# untitled.net
KiCad netlist of a schematic drawn in EAGLE
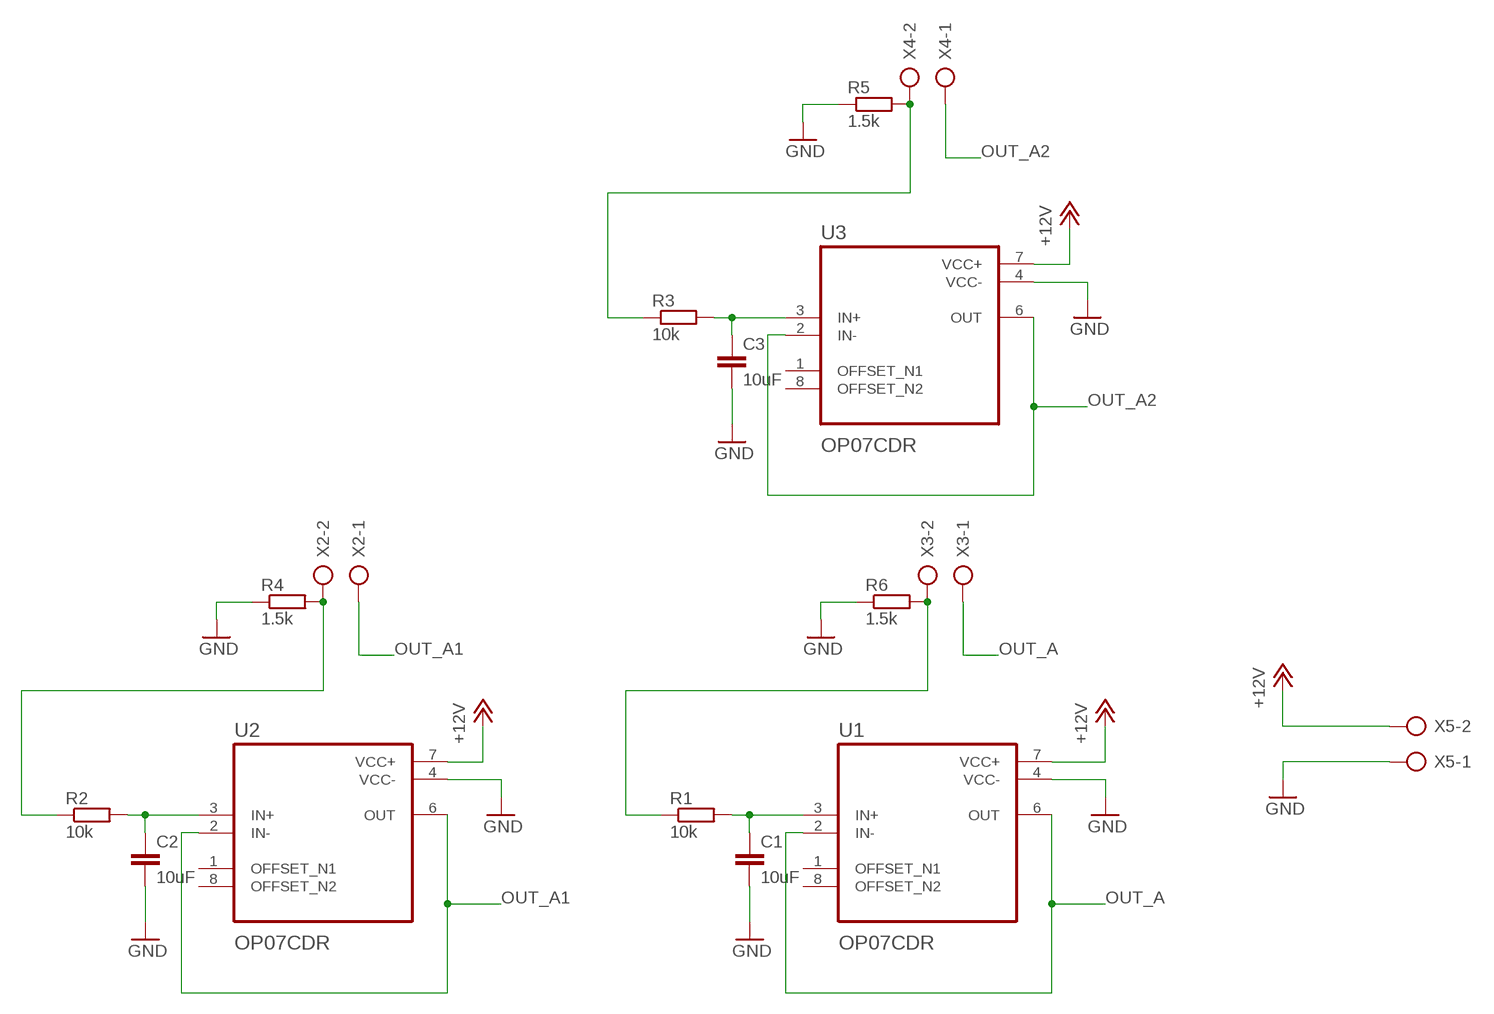
[diagram p0: schematic, sheet 1]

(export (version "E")
  (design (tool "Eeschema 10.0.6"))
  (components
    (comp (ref "C1")
      (value "10uF")
      (footprint "eagle-import:C0805")
      (libsource (lib "eagle-import") (part "C-EUC0805"))
    )
    (comp (ref "C2")
      (value "10uF")
      (footprint "eagle-import:C0805")
      (libsource (lib "eagle-import") (part "C-EUC0805"))
    )
    (comp (ref "C3")
      (value "10uF")
      (footprint "eagle-import:C0805")
      (libsource (lib "eagle-import") (part "C-EUC0805"))
    )
    (comp (ref "R1")
      (value "10k")
      (footprint "eagle-import:M0805")
      (libsource (lib "eagle-import") (part "R-EU_M0805"))
    )
    (comp (ref "R2")
      (value "10k")
      (footprint "eagle-import:M0805")
      (libsource (lib "eagle-import") (part "R-EU_M0805"))
    )
    (comp (ref "R3")
      (value "10k")
      (footprint "eagle-import:M0805")
      (libsource (lib "eagle-import") (part "R-EU_M0805"))
    )
    (comp (ref "R4")
      (value "1.5k")
      (footprint "eagle-import:M0805")
      (libsource (lib "eagle-import") (part "R-EU_M0805"))
    )
    (comp (ref "R5")
      (value "1.5k")
      (footprint "eagle-import:M0805")
      (libsource (lib "eagle-import") (part "R-EU_M0805"))
    )
    (comp (ref "R6")
      (value "1.5k")
      (footprint "eagle-import:M0805")
      (libsource (lib "eagle-import") (part "R-EU_M0805"))
    )
    (comp (ref "U1")
      (value "OP07CDR")
      (footprint "eagle-import:SOIC127P599X175-8N")
      (fields (field (name "MF") "Texas Instruments"))
      (libsource (lib "eagle-import") (part "OP07CDR"))
    )
    (comp (ref "U2")
      (value "OP07CDR")
      (footprint "eagle-import:SOIC127P599X175-8N")
      (fields (field (name "MF") "Texas Instruments"))
      (libsource (lib "eagle-import") (part "OP07CDR"))
    )
    (comp (ref "U3")
      (value "OP07CDR")
      (footprint "eagle-import:SOIC127P599X175-8N")
      (fields (field (name "MF") "Texas Instruments"))
      (libsource (lib "eagle-import") (part "OP07CDR"))
    )
    (comp (ref "X2")
      (value "AK500/2")
      (footprint "eagle-import:AK500_2")
      (libsource (lib "eagle-import") (part "AK500/2"))
    )
    (comp (ref "X3")
      (value "AK500/2")
      (footprint "eagle-import:AK500_2")
      (libsource (lib "eagle-import") (part "AK500/2"))
    )
    (comp (ref "X4")
      (value "AK500/2")
      (footprint "eagle-import:AK500_2")
      (libsource (lib "eagle-import") (part "AK500/2"))
    )
    (comp (ref "X5")
      (value "AK500/2")
      (footprint "eagle-import:AK500_2")
      (libsource (lib "eagle-import") (part "AK500/2"))
    )
  )
  (nets
    (net (code "1") (name "+12V") (class "Default")
      (node (ref "U1") (pin "7") (pinfunction "VCC+_7") (pintype "power_in"))
      (node (ref "U2") (pin "7") (pinfunction "VCC+_7") (pintype "power_in"))
      (node (ref "U3") (pin "7") (pinfunction "VCC+_7") (pintype "power_in"))
      (node (ref "X5") (pin "2") (pinfunction "KL_2") (pintype "passive"))
    )
    (net (code "2") (name "/OUT_A") (class "Default")
      (node (ref "U1") (pin "2") (pinfunction "IN-_2") (pintype "input"))
      (node (ref "U1") (pin "6") (pinfunction "OUT_6") (pintype "output"))
      (node (ref "X3") (pin "1") (pinfunction "KL_1") (pintype "passive"))
    )
    (net (code "3") (name "/OUT_A1") (class "Default")
      (node (ref "U2") (pin "2") (pinfunction "IN-_2") (pintype "input"))
      (node (ref "U2") (pin "6") (pinfunction "OUT_6") (pintype "output"))
      (node (ref "X2") (pin "1") (pinfunction "KL_1") (pintype "passive"))
    )
    (net (code "4") (name "/OUT_A2") (class "Default")
      (node (ref "U3") (pin "2") (pinfunction "IN-_2") (pintype "input"))
      (node (ref "U3") (pin "6") (pinfunction "OUT_6") (pintype "output"))
      (node (ref "X4") (pin "1") (pinfunction "KL_1") (pintype "passive"))
    )
    (net (code "5") (name "GND") (class "Default")
      (node (ref "C1") (pin "2") (pinfunction "2_2") (pintype "passive"))
      (node (ref "C2") (pin "2") (pinfunction "2_2") (pintype "passive"))
      (node (ref "C3") (pin "2") (pinfunction "2_2") (pintype "passive"))
      (node (ref "R4") (pin "1") (pinfunction "1_1") (pintype "passive"))
      (node (ref "R5") (pin "1") (pinfunction "1_1") (pintype "passive"))
      (node (ref "R6") (pin "1") (pinfunction "1_1") (pintype "passive"))
      (node (ref "U1") (pin "4") (pinfunction "VCC-_4") (pintype "power_in"))
      (node (ref "U2") (pin "4") (pinfunction "VCC-_4") (pintype "power_in"))
      (node (ref "U3") (pin "4") (pinfunction "VCC-_4") (pintype "power_in"))
      (node (ref "X5") (pin "1") (pinfunction "KL_1") (pintype "passive"))
    )
    (net (code "6") (name "Net-(U1-IN+)") (class "Default")
      (node (ref "C1") (pin "1") (pinfunction "1_1") (pintype "passive"))
      (node (ref "R1") (pin "2") (pinfunction "2_2") (pintype "passive"))
      (node (ref "U1") (pin "3") (pinfunction "IN+_3") (pintype "input"))
    )
    (net (code "7") (name "Net-(U2-IN+)") (class "Default")
      (node (ref "C2") (pin "1") (pinfunction "1_1") (pintype "passive"))
      (node (ref "R2") (pin "2") (pinfunction "2_2") (pintype "passive"))
      (node (ref "U2") (pin "3") (pinfunction "IN+_3") (pintype "input"))
    )
    (net (code "8") (name "Net-(U3-IN+)") (class "Default")
      (node (ref "C3") (pin "1") (pinfunction "1_1") (pintype "passive"))
      (node (ref "R3") (pin "2") (pinfunction "2_2") (pintype "passive"))
      (node (ref "U3") (pin "3") (pinfunction "IN+_3") (pintype "input"))
    )
    (net (code "9") (name "Net-(X2B-KL)") (class "Default")
      (node (ref "R2") (pin "1") (pinfunction "1_1") (pintype "passive"))
      (node (ref "R4") (pin "2") (pinfunction "2_2") (pintype "passive"))
      (node (ref "X2") (pin "2") (pinfunction "KL_2") (pintype "passive"))
    )
    (net (code "10") (name "Net-(X3B-KL)") (class "Default")
      (node (ref "R1") (pin "1") (pinfunction "1_1") (pintype "passive"))
      (node (ref "R6") (pin "2") (pinfunction "2_2") (pintype "passive"))
      (node (ref "X3") (pin "2") (pinfunction "KL_2") (pintype "passive"))
    )
    (net (code "11") (name "Net-(X4B-KL)") (class "Default")
      (node (ref "R3") (pin "1") (pinfunction "1_1") (pintype "passive"))
      (node (ref "R5") (pin "2") (pinfunction "2_2") (pintype "passive"))
      (node (ref "X4") (pin "2") (pinfunction "KL_2") (pintype "passive"))
    )
    (net (code "12") (name "unconnected-(U1-OFFSET_N1-Pad1)") (class "Default")
      (node (ref "U1") (pin "1") (pinfunction "OFFSET_N1_1") (pintype "bidirectional"))
    )
    (net (code "13") (name "unconnected-(U1-OFFSET_N2-Pad8)") (class "Default")
      (node (ref "U1") (pin "8") (pinfunction "OFFSET_N2_8") (pintype "bidirectional"))
    )
    (net (code "14") (name "unconnected-(U2-OFFSET_N1-Pad1)") (class "Default")
      (node (ref "U2") (pin "1") (pinfunction "OFFSET_N1_1") (pintype "bidirectional"))
    )
    (net (code "15") (name "unconnected-(U2-OFFSET_N2-Pad8)") (class "Default")
      (node (ref "U2") (pin "8") (pinfunction "OFFSET_N2_8") (pintype "bidirectional"))
    )
    (net (code "16") (name "unconnected-(U3-OFFSET_N1-Pad1)") (class "Default")
      (node (ref "U3") (pin "1") (pinfunction "OFFSET_N1_1") (pintype "bidirectional"))
    )
    (net (code "17") (name "unconnected-(U3-OFFSET_N2-Pad8)") (class "Default")
      (node (ref "U3") (pin "8") (pinfunction "OFFSET_N2_8") (pintype "bidirectional"))
    )
  )
)
